# I2C_IR.net
KiCad netlist of a schematic drawn in EAGLE
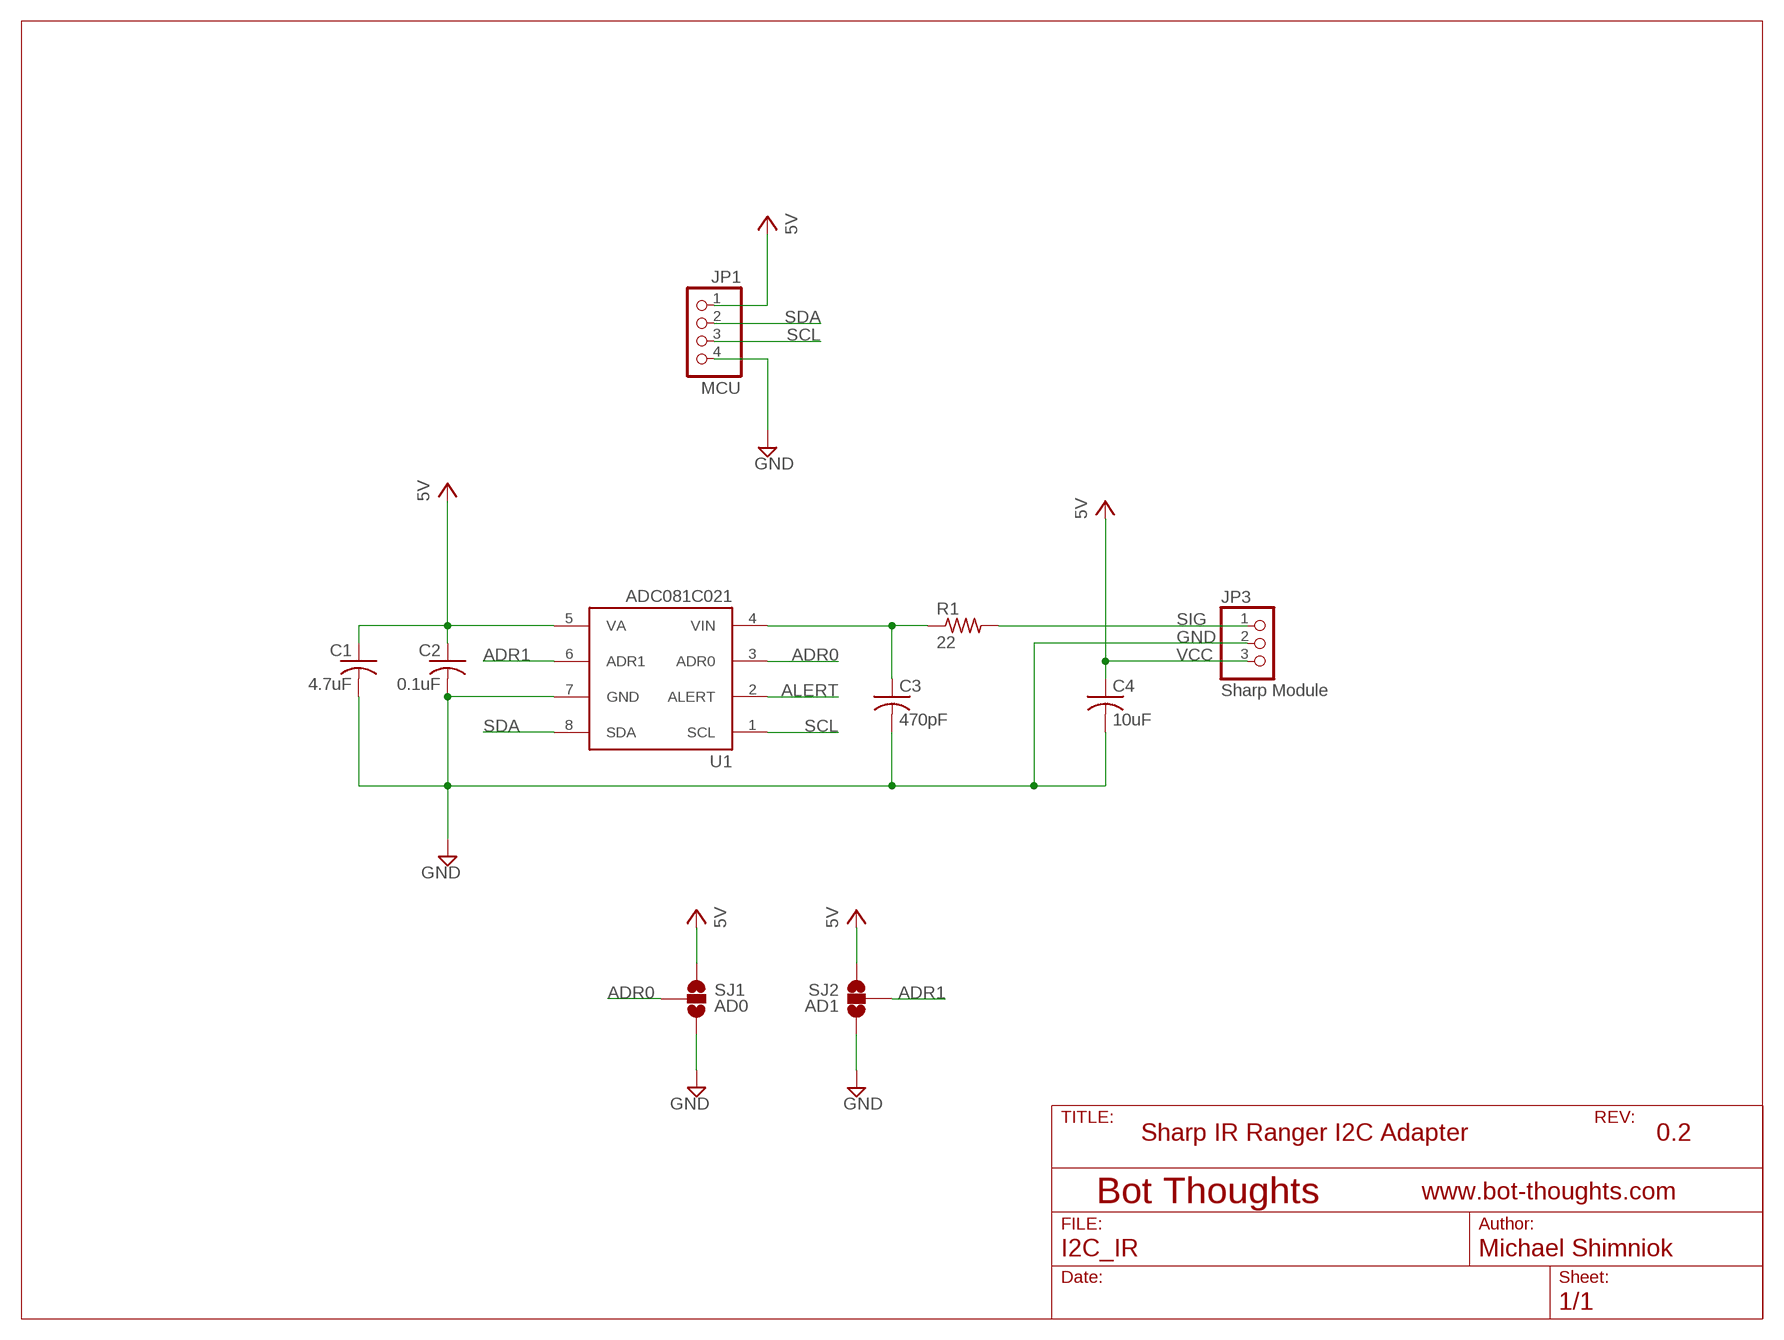
[diagram p0: schematic, sheet 1]

(export (version "E")
  (design (tool "Eeschema 10.0.6"))
  (components
    (comp (ref "C1")
      (value "4.7uF")
      (footprint "eagle-import:C0805K")
      (fields (field (name "PARTNO") "T491A475K010AT"))
      (libsource (lib "eagle-import") (part "C-USC0805K"))
    )
    (comp (ref "C2")
      (value "0.1uF")
      (footprint "eagle-import:C0603")
      (libsource (lib "eagle-import") (part "C-USC0603"))
    )
    (comp (ref "C3")
      (value "470pF")
      (footprint "eagle-import:C0603")
      (libsource (lib "eagle-import") (part "C-USC0603"))
    )
    (comp (ref "C4")
      (value "10uF")
      (footprint "eagle-import:C0805K")
      (libsource (lib "eagle-import") (part "C-USC0805K"))
    )
    (comp (ref "JP1")
      (value "MCU")
      (footprint "eagle-import:1X04-S")
      (libsource (lib "eagle-import") (part "PINHD-1X04_2.54-S"))
    )
    (comp (ref "JP3")
      (value "Sharp Module")
      (footprint "eagle-import:1X03M")
      (libsource (lib "eagle-import") (part "PINHD-1X03_2.00"))
    )
    (comp (ref "R1")
      (value "22")
      (footprint "eagle-import:R0603")
      (libsource (lib "eagle-import") (part "R-US_R0603"))
    )
    (comp (ref "SJ1")
      (value "AD0")
      (footprint "eagle-import:SJ_3")
      (libsource (lib "eagle-import") (part "SOLDERJUMPER_2WAYS"))
    )
    (comp (ref "SJ2")
      (value "AD1")
      (footprint "eagle-import:SJ_3")
      (libsource (lib "eagle-import") (part "SOLDERJUMPER_2WAYS"))
    )
    (comp (ref "U1")
      (value "ADC081C021")
      (footprint "eagle-import:MSOP8_0.65")
      (libsource (lib "eagle-import") (part "ADC081C021"))
    )
  )
  (nets
    (net (code "1") (name "/ADR0") (class "Default")
      (node (ref "SJ1") (pin "2") (pinfunction "2_2") (pintype "passive"))
      (node (ref "U1") (pin "3") (pinfunction "ADR0_3") (pintype "bidirectional"))
    )
    (net (code "2") (name "/ADR1") (class "Default")
      (node (ref "SJ2") (pin "2") (pinfunction "2_2") (pintype "passive"))
      (node (ref "U1") (pin "6") (pinfunction "ADR1_6") (pintype "bidirectional"))
    )
    (net (code "3") (name "/ALERT") (class "Default")
      (node (ref "U1") (pin "2") (pinfunction "ALERT_2") (pintype "bidirectional"))
    )
    (net (code "4") (name "/SCL") (class "Default")
      (node (ref "JP1") (pin "3") (pinfunction "3_3") (pintype "passive"))
      (node (ref "U1") (pin "1") (pinfunction "SCL_1") (pintype "bidirectional"))
    )
    (net (code "5") (name "/SDA") (class "Default")
      (node (ref "JP1") (pin "2") (pinfunction "2_2") (pintype "passive"))
      (node (ref "U1") (pin "8") (pinfunction "SDA_8") (pintype "bidirectional"))
    )
    (net (code "6") (name "/SIG") (class "Default")
      (node (ref "JP3") (pin "1") (pinfunction "1_1") (pintype "passive"))
      (node (ref "R1") (pin "2") (pinfunction "2_2") (pintype "passive"))
    )
    (net (code "7") (name "5V") (class "Default")
      (node (ref "C1") (pin "1") (pinfunction "1_1") (pintype "passive"))
      (node (ref "C2") (pin "1") (pinfunction "1_1") (pintype "passive"))
      (node (ref "C4") (pin "1") (pinfunction "1_1") (pintype "passive"))
      (node (ref "JP1") (pin "1") (pinfunction "1_1") (pintype "passive"))
      (node (ref "JP3") (pin "3") (pinfunction "3_3") (pintype "passive"))
      (node (ref "SJ1") (pin "1") (pinfunction "1_1") (pintype "passive"))
      (node (ref "SJ2") (pin "1") (pinfunction "1_1") (pintype "passive"))
      (node (ref "U1") (pin "5") (pinfunction "VA_5") (pintype "bidirectional"))
    )
    (net (code "8") (name "GND") (class "Default")
      (node (ref "C1") (pin "2") (pinfunction "2_2") (pintype "passive"))
      (node (ref "C2") (pin "2") (pinfunction "2_2") (pintype "passive"))
      (node (ref "C3") (pin "2") (pinfunction "2_2") (pintype "passive"))
      (node (ref "C4") (pin "2") (pinfunction "2_2") (pintype "passive"))
      (node (ref "JP1") (pin "4") (pinfunction "4_4") (pintype "passive"))
      (node (ref "JP3") (pin "2") (pinfunction "2_2") (pintype "passive"))
      (node (ref "SJ1") (pin "3") (pinfunction "3_3") (pintype "passive"))
      (node (ref "SJ2") (pin "3") (pinfunction "3_3") (pintype "passive"))
      (node (ref "U1") (pin "7") (pinfunction "GND_7") (pintype "bidirectional"))
    )
    (net (code "9") (name "Net-(U1-VIN)") (class "Default")
      (node (ref "C3") (pin "1") (pinfunction "1_1") (pintype "passive"))
      (node (ref "R1") (pin "1") (pinfunction "1_1") (pintype "passive"))
      (node (ref "U1") (pin "4") (pinfunction "VIN_4") (pintype "bidirectional"))
    )
  )
)
